# Power.net
KiCad netlist of a schematic drawn in Altium Designer
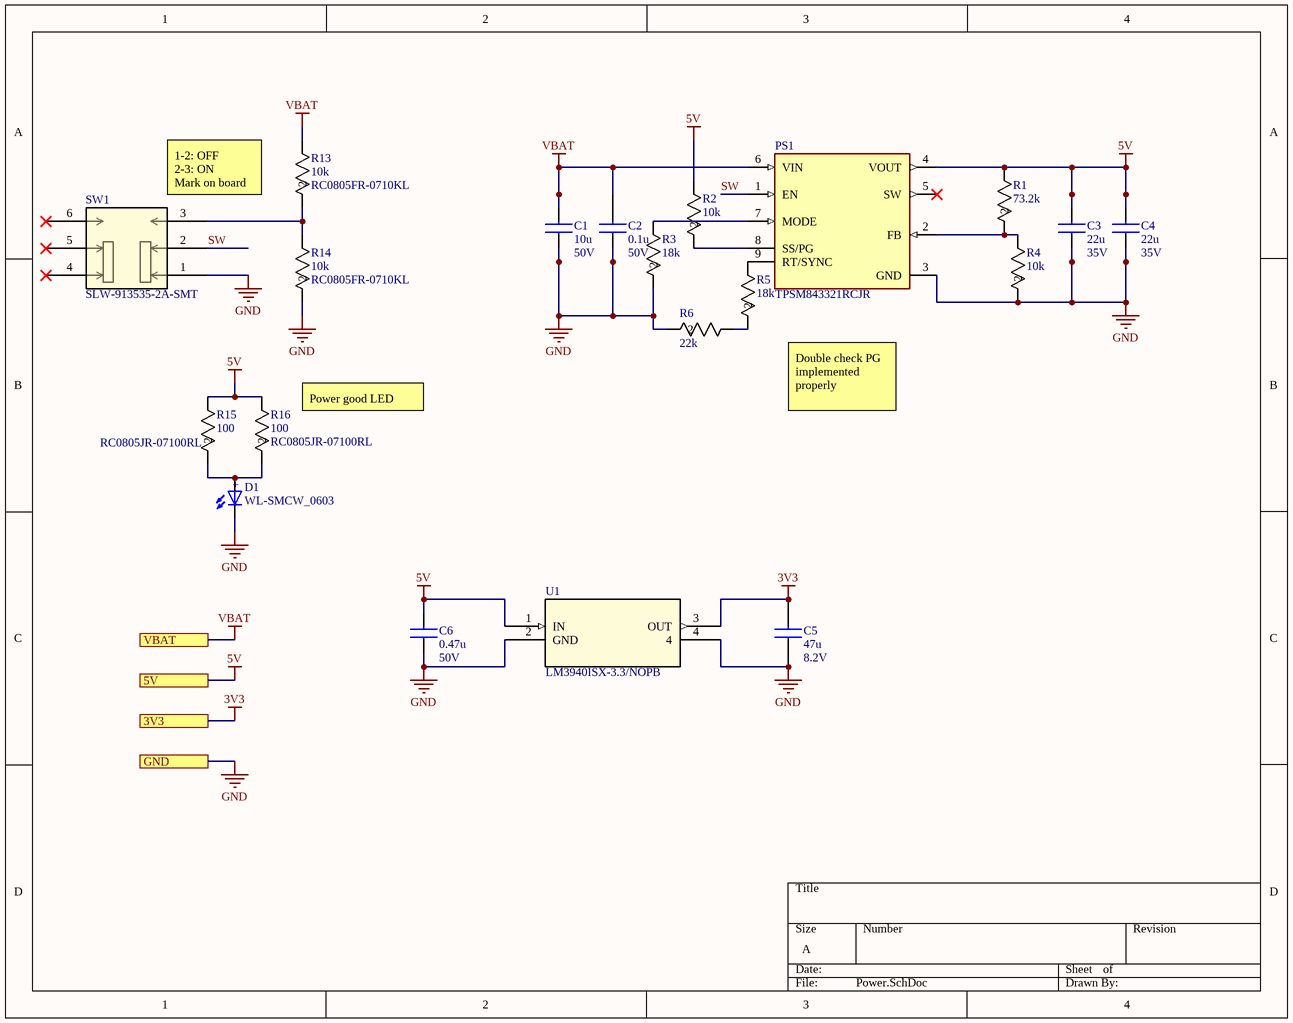
[diagram p0: Power.SchDoc]

(export (version "E")
  (design (tool "Eeschema 10.0.6"))
  (components
    (comp (ref "C1")
      (value "10u")
      (footprint "CAPC2012X145N")
      (description "Multilayer Ceramic Chip Capacitors, Capacitance=10?F, LxWxT:2x1.25x1.25mm")
      (fields
        (field (name "MOUSER PART NUMBER") "810-C2012X5R1H106K12")
        (field (name "MANUFACTURER_PART_NUMBER") "C2012X5R1H106K125AC")
        (field (name "RATED VOLTAGE") "50V")
      )
      (libsource (lib "Caps") (part "C2012X5R1H106K125AC"))
    )
    (comp (ref "C2")
      (value "0.1u")
      (footprint "CAPC2012X145N")
      (description "Multilayer Ceramic Chip Capacitors, Capacitance=0.1u")
      (fields
        (field (name "MANUFACTURER_PART_NUMBER") "KAM21BR71H104JM")
        (field (name "RATED VOLTAGE") "50V")
      )
      (libsource (lib "Caps") (part "KAM21BR71H104JM"))
    )
    (comp (ref "C3")
      (value "22u")
      (footprint "CAPC2012X145N")
      (description "Multilayer Ceramic Chip Capacitors, Capacitance=22u")
      (fields
        (field (name "MANUFACTURER_PART_NUMBER") "C2012X5R1V226M125AC")
        (field (name "RATED VOLTAGE") "35V")
      )
      (libsource (lib "Caps") (part "C2012X5R1V226M125AC"))
    )
    (comp (ref "C4")
      (value "22u")
      (footprint "CAPC2012X145N")
      (description "Multilayer Ceramic Chip Capacitors, Capacitance=22u")
      (fields
        (field (name "MANUFACTURER_PART_NUMBER") "C2012X5R1V226M125AC")
        (field (name "RATED VOLTAGE") "35V")
      )
      (libsource (lib "Caps") (part "C2012X5R1V226M125AC"))
    )
    (comp (ref "C5")
      (value "47u")
      (footprint "CAPC2012X145N")
      (description "47 µF Molded Tantalum Polymer Capacitor 8.2 V 0805 (2012 Metric) 500mOhm @ 100kHz")
      (fields
        (field (name "MANUFACTURER_PART_NUMBER") "T58W0476M8R2C0500")
        (field (name "RATED VOLTAGE") "8.2V")
      )
      (libsource (lib "Caps") (part "T58W0476M8R2C0500"))
    )
    (comp (ref "C6")
      (value "0.47u")
      (footprint "CAPC2012X145N")
      (description "Multilayer Ceramic Chip Capacitors, Capacitance=0.47u")
      (fields
        (field (name "MANUFACTURER_PART_NUMBER") "GCM21BR71H474KA55K")
        (field (name "RATED VOLTAGE") "50V")
      )
      (libsource (lib "Caps") (part "GCM21BR71H474KA55K"))
    )
    (comp (ref "D1")
      (value "WL-SMCW_0603")
      (footprint "WL-SMCW_0603")
      (description "0603, Green Typ.(@20mA): 520nm, 430mcd, 3.2V, 140Â° InGaN")
      (fields (field (name "MF") "Wurth Electronics") (field (name "MP") "150060GS75000"))
      (libsource (lib "WL-SMCW_0603") (part "WL-SMCW_0603"))
    )
    (comp (ref "PS1")
      (value "TPSM843321RCJR")
      (footprint "MODULE_TPSM843321RCJR")
      (description "Non-Isolated PoL Module DC DC Converter 1 Output 5V 3A 3.8V - 18V Input")
      (fields (field (name "MF") "Texas Instruments"))
      (libsource (lib "TPSM843321RCJR") (part "TPSM843321RCJR"))
    )
    (comp (ref "R1")
      (value "73.2k")
      (footprint "RC0805N_YAG")
      (description "RES 0805 73.2k 1% 1/8W")
      (fields (field (name "MANUFACTURER_PART_NUMBER") "RC0805FR-0773K2L") (field (name "TOLERANCE") "1%"))
      (libsource (lib "Resistors") (part "RC0805FR-0773K2L"))
    )
    (comp (ref "R2")
      (value "10k")
      (footprint "RC0805N_YAG")
      (description "RES 0805 10k 1% 1/8W")
      (fields (field (name "MANUFACTURER_PART_NUMBER") "RC0805FR-0710KL") (field (name "TOLERANCE") "1%"))
      (libsource (lib "Resistors") (part "RC0805FR-0710KL"))
    )
    (comp (ref "R3")
      (value "18k")
      (footprint "RC0805N_YAG")
      (description "RES 0805 18k 1% 1/8W")
      (fields (field (name "MANUFACTURER_PART_NUMBER") "RC0805FR-0718KL") (field (name "TOLERANCE") "1%"))
      (libsource (lib "Resistors") (part "RC0805FR-0718KL"))
    )
    (comp (ref "R4")
      (value "10k")
      (footprint "RC0805N_YAG")
      (description "RES 0805 10k 1% 1/8W")
      (fields (field (name "MANUFACTURER_PART_NUMBER") "RC0805FR-0710KL") (field (name "TOLERANCE") "1%"))
      (libsource (lib "Resistors") (part "RC0805FR-0710KL"))
    )
    (comp (ref "R5")
      (value "18k")
      (footprint "RC0805N_YAG")
      (description "RES 0805 18k 1% 1/8W")
      (fields (field (name "MANUFACTURER_PART_NUMBER") "RC0805FR-0718KL") (field (name "TOLERANCE") "1%"))
      (libsource (lib "Resistors") (part "RC0805FR-0718KL"))
    )
    (comp (ref "R6")
      (value "22k")
      (footprint "RC0805N_YAG")
      (description "RES 0805 22k 1% 1/8W")
      (fields (field (name "MANUFACTURER_PART_NUMBER") "RC0805FR-0722KL") (field (name "TOLERANCE") "1%"))
      (libsource (lib "Resistors") (part "RC0805FR-0722KL"))
    )
    (comp (ref "R13")
      (value "RC0805FR-0710KL")
      (footprint "RC0805N_YAG")
      (description "RES 0805 10k 1% 1/8W")
      (fields (field (name "TOLERANCE") "1%") (field (name "ALTIUM_VALUE") "10k"))
      (libsource (lib "Resistors") (part "RC0805FR-0710KL"))
    )
    (comp (ref "R14")
      (value "RC0805FR-0710KL")
      (footprint "RC0805N_YAG")
      (description "RES 0805 10k 1% 1/8W")
      (fields (field (name "TOLERANCE") "1%") (field (name "ALTIUM_VALUE") "10k"))
      (libsource (lib "Resistors") (part "RC0805FR-0710KL"))
    )
    (comp (ref "R15")
      (value "RC0805JR-07100RL")
      (footprint "RC0805N_YAG")
      (description "RES 0805 100 5% 1/8W")
      (fields (field (name "TOLERANCE") "5%") (field (name "ALTIUM_VALUE") "100"))
      (libsource (lib "Resistors") (part "RC0805JR-07100RL"))
    )
    (comp (ref "R16")
      (value "RC0805JR-07100RL")
      (footprint "RC0805N_YAG")
      (description "RES 0805 100 5% 1/8W")
      (fields (field (name "TOLERANCE") "5%") (field (name "ALTIUM_VALUE") "100"))
      (libsource (lib "Resistors") (part "RC0805JR-07100RL"))
    )
    (comp (ref "SW1")
      (value "SLW-913535-2A-SMT")
      (footprint "SLW-913535_CUD")
      (description "No Description Available")
      (fields (field (name "COPYRIGHT") "Copyright (C) 2025 Ultra Librarian. All rights reserved."))
      (libsource (lib "SLW-913535-2A-SMT") (part "SLW-913535-2A-SMT"))
    )
    (comp (ref "U1")
      (value "LM3940ISX-3.3/NOPB")
      (footprint "TS3B")
      (description "1-A, low-dropout voltage regulator for 5-V to 3.3-V conversion 3-DDPAK/TO-263 -40 to 125")
      (fields (field (name "COPYRIGHT") "Copyright (C) 2025 Ultra Librarian. All rights reserved."))
      (libsource (lib "LM3940ISX-3P3NOPB") (part "LM3940ISX-3.3NOPB"))
    )
  )
  (nets
    (net (code "1") (name "/SW") (class "Default")
      (node (ref "PS1") (pin "1") (pinfunction "EN_1") (pintype "input"))
      (node (ref "SW1") (pin "2") (pinfunction "2_2") (pintype "passive"))
    )
    (net (code "2") (name "3V3") (class "Default")
      (node (ref "C5") (pin "2") (pinfunction "2_2") (pintype "passive"))
      (node (ref "U1") (pin "3") (pinfunction "OUT_3") (pintype "output"))
    )
    (net (code "3") (name "5V") (class "Default")
      (node (ref "C3") (pin "2") (pinfunction "2_2") (pintype "passive"))
      (node (ref "C4") (pin "2") (pinfunction "2_2") (pintype "passive"))
      (node (ref "C6") (pin "2") (pinfunction "2_2") (pintype "passive"))
      (node (ref "PS1") (pin "4") (pinfunction "VOUT_4") (pintype "output"))
      (node (ref "R1") (pin "1") (pinfunction "1_1") (pintype "passive"))
      (node (ref "R15") (pin "1") (pinfunction "1_1") (pintype "passive"))
      (node (ref "R16") (pin "1") (pinfunction "1_1") (pintype "passive"))
      (node (ref "R2") (pin "1") (pinfunction "1_1") (pintype "passive"))
      (node (ref "U1") (pin "1") (pinfunction "IN_1") (pintype "input"))
    )
    (net (code "4") (name "GND") (class "Default")
      (node (ref "C1") (pin "1") (pinfunction "1_1") (pintype "passive"))
      (node (ref "C2") (pin "1") (pinfunction "1_1") (pintype "passive"))
      (node (ref "C3") (pin "1") (pinfunction "1_1") (pintype "passive"))
      (node (ref "C4") (pin "1") (pinfunction "1_1") (pintype "passive"))
      (node (ref "C5") (pin "1") (pinfunction "1_1") (pintype "passive"))
      (node (ref "C6") (pin "1") (pinfunction "1_1") (pintype "passive"))
      (node (ref "D1") (pin "1") (pinfunction "NEG_1") (pintype "passive"))
      (node (ref "PS1") (pin "3") (pinfunction "GND_3") (pintype "power_in"))
      (node (ref "R14") (pin "2") (pinfunction "2_2") (pintype "passive"))
      (node (ref "R3") (pin "2") (pinfunction "2_2") (pintype "passive"))
      (node (ref "R4") (pin "2") (pinfunction "2_2") (pintype "passive"))
      (node (ref "R6") (pin "2") (pinfunction "2_2") (pintype "passive"))
      (node (ref "SW1") (pin "1") (pinfunction "1_1") (pintype "passive"))
      (node (ref "U1") (pin "2") (pinfunction "GND_2") (pintype "passive"))
      (node (ref "U1") (pin "4") (pinfunction "4_4") (pintype "passive"))
    )
    (net (code "5") (name "Net-(D1-POS)") (class "Default")
      (node (ref "D1") (pin "2") (pinfunction "POS_2") (pintype "passive"))
      (node (ref "R15") (pin "2") (pinfunction "2_2") (pintype "passive"))
      (node (ref "R16") (pin "2") (pinfunction "2_2") (pintype "passive"))
    )
    (net (code "6") (name "Net-(PS1-FB)") (class "Default")
      (node (ref "PS1") (pin "2") (pinfunction "FB_2") (pintype "input"))
      (node (ref "R1") (pin "2") (pinfunction "2_2") (pintype "passive"))
      (node (ref "R4") (pin "1") (pinfunction "1_1") (pintype "passive"))
    )
    (net (code "7") (name "Net-(PS1-MODE)") (class "Default")
      (node (ref "PS1") (pin "7") (pinfunction "MODE_7") (pintype "input"))
      (node (ref "R3") (pin "1") (pinfunction "1_1") (pintype "passive"))
    )
    (net (code "8") (name "Net-(PS1-RT{slash}SYNC)") (class "Default")
      (node (ref "PS1") (pin "9") (pinfunction "RT/SYNC_9") (pintype "passive"))
      (node (ref "R5") (pin "1") (pinfunction "1_1") (pintype "passive"))
    )
    (net (code "9") (name "Net-(PS1-SS{slash}PG)") (class "Default")
      (node (ref "PS1") (pin "8") (pinfunction "SS/PG_8") (pintype "passive"))
      (node (ref "R2") (pin "2") (pinfunction "2_2") (pintype "passive"))
    )
    (net (code "10") (name "Net-(R5-Pad2)") (class "Default")
      (node (ref "R5") (pin "2") (pinfunction "2_2") (pintype "passive"))
      (node (ref "R6") (pin "1") (pinfunction "1_1") (pintype "passive"))
    )
    (net (code "11") (name "Net-(R13-Pad2)") (class "Default")
      (node (ref "R13") (pin "2") (pinfunction "2_2") (pintype "passive"))
      (node (ref "R14") (pin "1") (pinfunction "1_1") (pintype "passive"))
      (node (ref "SW1") (pin "3") (pinfunction "3_3") (pintype "passive"))
    )
    (net (code "12") (name "VBAT") (class "Default")
      (node (ref "C1") (pin "2") (pinfunction "2_2") (pintype "passive"))
      (node (ref "C2") (pin "2") (pinfunction "2_2") (pintype "passive"))
      (node (ref "PS1") (pin "6") (pinfunction "VIN_6") (pintype "input"))
      (node (ref "R13") (pin "1") (pinfunction "1_1") (pintype "passive"))
    )
    (net (code "13") (name "unconnected-(PS1-SW-Pad5)") (class "Default")
      (node (ref "PS1") (pin "5") (pinfunction "SW_5") (pintype "output+no_connect"))
    )
    (net (code "14") (name "unconnected-(SW1-Pad4)") (class "Default")
      (node (ref "SW1") (pin "4") (pinfunction "4_4") (pintype "passive+no_connect"))
    )
    (net (code "15") (name "unconnected-(SW1-Pad5)") (class "Default")
      (node (ref "SW1") (pin "5") (pinfunction "5_5") (pintype "passive+no_connect"))
    )
    (net (code "16") (name "unconnected-(SW1-Pad6)") (class "Default")
      (node (ref "SW1") (pin "6") (pinfunction "6_6") (pintype "passive+no_connect"))
    )
  )
)
